# IPNS_v0_2.net
KiCad netlist of a schematic drawn in EAGLE
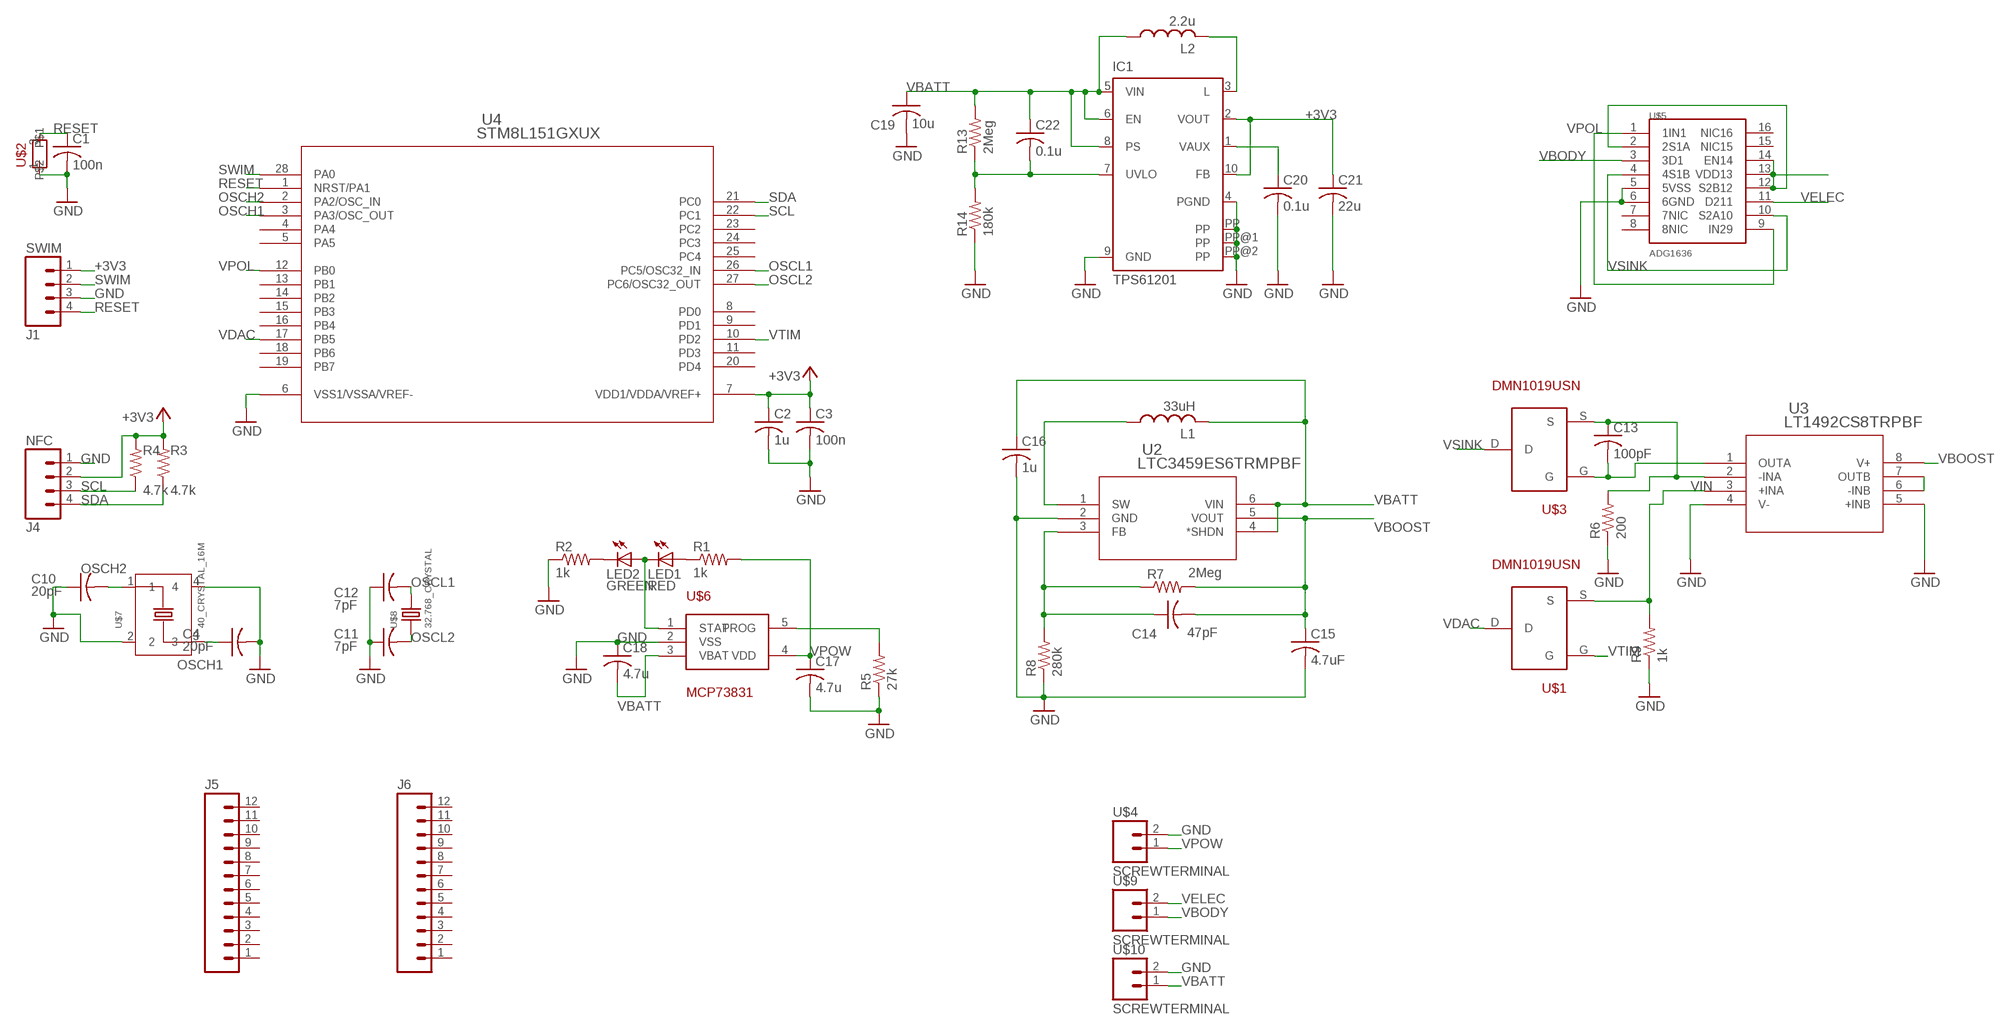
[diagram p0: schematic, sheet 1]

(export (version "E")
  (design (tool "Eeschema 10.0.6"))
  (components
    (comp (ref "C1")
      (value "100n")
      (footprint "eagle-import:C0603")
      (libsource (lib "eagle-import") (part "IPNS_Lib_v0.1_C-USC0603"))
    )
    (comp (ref "C2")
      (value "1u")
      (footprint "eagle-import:C0603")
      (libsource (lib "eagle-import") (part "IPNS_Lib_v0.1_C-USC0603"))
    )
    (comp (ref "C3")
      (value "100n")
      (footprint "eagle-import:C0603")
      (libsource (lib "eagle-import") (part "IPNS_Lib_v0.1_C-USC0603"))
    )
    (comp (ref "C4")
      (value "20pF")
      (footprint "eagle-import:C0603")
      (libsource (lib "eagle-import") (part "IPNS_Lib_v0.1_C-USC0603"))
    )
    (comp (ref "C10")
      (value "20pF")
      (footprint "eagle-import:C0603")
      (libsource (lib "eagle-import") (part "IPNS_Lib_v0.1_C-USC0603"))
    )
    (comp (ref "C11")
      (value "7pF")
      (footprint "eagle-import:C0603")
      (libsource (lib "eagle-import") (part "IPNS_Lib_v0.1_C-USC0603"))
    )
    (comp (ref "C12")
      (value "7pF")
      (footprint "eagle-import:C0603")
      (libsource (lib "eagle-import") (part "IPNS_Lib_v0.1_C-USC0603"))
    )
    (comp (ref "C13")
      (value "100pF")
      (footprint "eagle-import:C0603")
      (libsource (lib "eagle-import") (part "IPNS_Lib_v0.1_C-USC0603"))
    )
    (comp (ref "C14")
      (value "47pF")
      (footprint "eagle-import:C0603")
      (libsource (lib "eagle-import") (part "IPNS_Lib_v0.1_C-USC0603"))
    )
    (comp (ref "C15")
      (value "4.7uF")
      (footprint "eagle-import:C0603")
      (libsource (lib "eagle-import") (part "IPNS_Lib_v0.1_C-USC0603"))
    )
    (comp (ref "C16")
      (value "1u")
      (footprint "eagle-import:C0603")
      (libsource (lib "eagle-import") (part "IPNS_Lib_v0.1_C-USC0603"))
    )
    (comp (ref "C17")
      (value "4.7u")
      (footprint "eagle-import:C0603")
      (libsource (lib "eagle-import") (part "C-USC0603"))
    )
    (comp (ref "C18")
      (value "4.7u")
      (footprint "eagle-import:C0603")
      (libsource (lib "eagle-import") (part "C-USC0603"))
    )
    (comp (ref "C19")
      (value "10u")
      (footprint "eagle-import:C0603")
      (libsource (lib "eagle-import") (part "C-USC0603"))
    )
    (comp (ref "C20")
      (value "0.1u")
      (footprint "eagle-import:C0603")
      (libsource (lib "eagle-import") (part "rcl_C-USC0603"))
    )
    (comp (ref "C21")
      (value "22u")
      (footprint "eagle-import:C0603")
      (libsource (lib "eagle-import") (part "rcl_C-USC0603"))
    )
    (comp (ref "C22")
      (value "0.1u")
      (footprint "eagle-import:C0603")
      (libsource (lib "eagle-import") (part "rcl_C-USC0603"))
    )
    (comp (ref "IC1")
      (value "TPS61201")
      (footprint "eagle-import:S-PDSO-N10")
      (fields (field (name "MPN") "TPS61200DRCT"))
      (libsource (lib "eagle-import") (part "TPS61200"))
    )
    (comp (ref "J1")
      (value "SWIM")
      (footprint "eagle-import:1X04")
      (libsource (lib "eagle-import") (part "M04PTH"))
    )
    (comp (ref "J4")
      (value "NFC")
      (footprint "eagle-import:1X04")
      (libsource (lib "eagle-import") (part "M04PTH"))
    )
    (comp (ref "J5")
      (value "M12PTH")
      (footprint "eagle-import:1X12")
      (libsource (lib "eagle-import") (part "M12PTH"))
    )
    (comp (ref "J6")
      (value "M12PTH")
      (footprint "eagle-import:1X12")
      (libsource (lib "eagle-import") (part "M12PTH"))
    )
    (comp (ref "L1")
      (value "33uH")
      (footprint "eagle-import:L2012C")
      (libsource (lib "eagle-import") (part "L-USL2012C"))
    )
    (comp (ref "L2")
      (value "2.2u")
      (footprint "eagle-import:L2012C")
      (libsource (lib "eagle-import") (part "rcl_L-USL2012C"))
    )
    (comp (ref "LED1")
      (value "RED")
      (footprint "eagle-import:SML0603")
      (libsource (lib "eagle-import") (part "LEDSML0603"))
    )
    (comp (ref "LED2")
      (value "GREEN")
      (footprint "eagle-import:SML0603")
      (libsource (lib "eagle-import") (part "LEDSML0603"))
    )
    (comp (ref "R1")
      (value "1k")
      (footprint "eagle-import:R0603")
      (libsource (lib "eagle-import") (part "R-US_R0603"))
    )
    (comp (ref "R2")
      (value "1k")
      (footprint "eagle-import:R0603")
      (libsource (lib "eagle-import") (part "R-US_R0603"))
    )
    (comp (ref "R3")
      (value "4.7k")
      (footprint "eagle-import:R0603")
      (libsource (lib "eagle-import") (part "IPNS_Lib_v0.1_R-US_R0603"))
    )
    (comp (ref "R4")
      (value "4.7k")
      (footprint "eagle-import:R0603")
      (libsource (lib "eagle-import") (part "IPNS_Lib_v0.1_R-US_R0603"))
    )
    (comp (ref "R5")
      (value "27k")
      (footprint "eagle-import:R0603")
      (libsource (lib "eagle-import") (part "R-US_R0603"))
    )
    (comp (ref "R6")
      (value "200")
      (footprint "eagle-import:R0603")
      (libsource (lib "eagle-import") (part "IPNS_Lib_v0.1_R-US_R0603"))
    )
    (comp (ref "R7")
      (value "2Meg")
      (footprint "eagle-import:R0603")
      (libsource (lib "eagle-import") (part "IPNS_Lib_v0.1_R-US_R0603"))
    )
    (comp (ref "R8")
      (value "280k")
      (footprint "eagle-import:R0603")
      (libsource (lib "eagle-import") (part "IPNS_Lib_v0.1_R-US_R0603"))
    )
    (comp (ref "R9")
      (value "1k")
      (footprint "eagle-import:R0603")
      (libsource (lib "eagle-import") (part "IPNS_Lib_v0.1_R-US_R0603"))
    )
    (comp (ref "R13")
      (value "2Meg")
      (footprint "eagle-import:R0603")
      (libsource (lib "eagle-import") (part "rcl_R-US_R0603"))
    )
    (comp (ref "R14")
      (value "180k")
      (footprint "eagle-import:R0603")
      (libsource (lib "eagle-import") (part "rcl_R-US_R0603"))
    )
    (comp (ref "U$1")
      (value "DMN1019USN")
      (footprint "eagle-import:DMN1019USN")
      (libsource (lib "eagle-import") (part "DMN1019USN"))
    )
    (comp (ref "U$2")
      (value "PUSH-BUTTON")
      (footprint "eagle-import:PUSH-BUTTON")
      (libsource (lib "eagle-import") (part "PUSH-BUTTON"))
    )
    (comp (ref "U$3")
      (value "DMN1019USN")
      (footprint "eagle-import:DMN1019USN")
      (libsource (lib "eagle-import") (part "DMN1019USN"))
    )
    (comp (ref "U$4")
      (value "SCREWTERMINAL")
      (footprint "eagle-import:SCREWTERMINAL")
      (libsource (lib "eagle-import") (part "SCREWTERMINAL"))
    )
    (comp (ref "U$5")
      (value "ADG1636")
      (footprint "eagle-import:TSSOP16")
      (libsource (lib "eagle-import") (part "ADG1636"))
    )
    (comp (ref "U$6")
      (value "MCP78381")
      (footprint "eagle-import:SOT23-5L")
      (libsource (lib "eagle-import") (part "MCP78381"))
    )
    (comp (ref "U$7")
      (value "40_CRYSTAL_16M")
      (footprint "eagle-import:X4-SMD-3.2X2.5X0.7MM")
      (libsource (lib "eagle-import") (part "40_CRYSTAL_16M"))
    )
    (comp (ref "U$8")
      (value "32.768_CRYSTAL")
      (footprint "eagle-import:X2-SMD-3.2X1.5X0.55MM")
      (libsource (lib "eagle-import") (part "32.768_CRYSTAL"))
    )
    (comp (ref "U$9")
      (value "SCREWTERMINAL")
      (footprint "eagle-import:SCREWTERMINAL")
      (libsource (lib "eagle-import") (part "SCREWTERMINAL"))
    )
    (comp (ref "U$10")
      (value "SCREWTERMINAL")
      (footprint "eagle-import:SCREWTERMINAL")
      (libsource (lib "eagle-import") (part "SCREWTERMINAL"))
    )
    (comp (ref "U2")
      (value "LTC3459ES6TRMPBF")
      (footprint "eagle-import:TSOT-23_S6")
      (fields
        (field (name "MANUFACTURER_PART_NUMBER") "ltc3459es6#trmpbf")
        (field (name "COPYRIGHT") "Copyright (C) 2016 Accelerated Designs. All rights reserved")
      )
      (libsource (lib "eagle-import") (part "LTC3459ES6TRMPBF"))
    )
    (comp (ref "U3")
      (value "LT1492CS8TRPBF")
      (footprint "eagle-import:SO-8_S")
      (fields (field (name "MANUFACTURER_PART_NUMBER") "lt1492cs8#trpbf"))
      (libsource (lib "eagle-import") (part "LT1492CS8TRPBF"))
    )
    (comp (ref "U4")
      (value "STM8L151GXUX")
      (footprint "eagle-import:UFQFPN-28")
      (fields
        (field (name "MANUFACTURER_PART_NUMBER") "stm8l151gxux")
        (field (name "COPYRIGHT") "Copyright (C) 2016 Accelerated Designs. All rights reserved")
      )
      (libsource (lib "eagle-import") (part "STM8L151GXUX"))
    )
  )
  (nets
    (net (code "1") (name "+3V3") (class "Default")
      (node (ref "C2") (pin "1") (pinfunction "1_1") (pintype "passive"))
      (node (ref "C21") (pin "1") (pinfunction "1_1") (pintype "passive"))
      (node (ref "C3") (pin "1") (pinfunction "1_1") (pintype "passive"))
      (node (ref "IC1") (pin "10") (pinfunction "FB_10") (pintype "input"))
      (node (ref "IC1") (pin "2") (pinfunction "VOUT_2") (pintype "passive"))
      (node (ref "J1") (pin "1") (pinfunction "1_1") (pintype "passive"))
      (node (ref "J4") (pin "2") (pinfunction "2_2") (pintype "passive"))
      (node (ref "R3") (pin "2") (pinfunction "2_2") (pintype "passive"))
      (node (ref "R4") (pin "2") (pinfunction "2_2") (pintype "passive"))
      (node (ref "U4") (pin "7") (pinfunction "VDD1/VDDA/VREF+_7") (pintype "power_in"))
    )
    (net (code "2") (name "/OSCH1") (class "Default")
      (node (ref "C4") (pin "1") (pinfunction "1_1") (pintype "passive"))
      (node (ref "U$7") (pin "3") (pinfunction "3_3") (pintype "bidirectional"))
      (node (ref "U4") (pin "3") (pinfunction "PA3/OSC_OUT_3") (pintype "bidirectional"))
    )
    (net (code "3") (name "/OSCH2") (class "Default")
      (node (ref "C10") (pin "2") (pinfunction "2_2") (pintype "passive"))
      (node (ref "U$7") (pin "1") (pinfunction "1_1") (pintype "bidirectional"))
      (node (ref "U4") (pin "2") (pinfunction "PA2/OSC_IN_2") (pintype "bidirectional"))
    )
    (net (code "4") (name "/OSCL1") (class "Default")
      (node (ref "C12") (pin "2") (pinfunction "2_2") (pintype "passive"))
      (node (ref "U$8") (pin "2") (pinfunction "2_2") (pintype "passive"))
      (node (ref "U4") (pin "26") (pinfunction "PC5/OSC32_IN_26") (pintype "bidirectional"))
    )
    (net (code "5") (name "/OSCL2") (class "Default")
      (node (ref "C11") (pin "2") (pinfunction "2_2") (pintype "passive"))
      (node (ref "U$8") (pin "1") (pinfunction "1_1") (pintype "passive"))
      (node (ref "U4") (pin "27") (pinfunction "PC6/OSC32_OUT_27") (pintype "bidirectional"))
    )
    (net (code "6") (name "/RESET") (class "Default")
      (node (ref "C1") (pin "1") (pinfunction "1_1") (pintype "passive"))
      (node (ref "J1") (pin "4") (pinfunction "4_4") (pintype "passive"))
      (node (ref "U$2") (pin "3") (pinfunction "P$2_3") (pintype "bidirectional"))
      (node (ref "U4") (pin "1") (pinfunction "NRST/PA1_1") (pintype "bidirectional"))
    )
    (net (code "7") (name "/SCL") (class "Default")
      (node (ref "J4") (pin "3") (pinfunction "3_3") (pintype "passive"))
      (node (ref "R4") (pin "1") (pinfunction "1_1") (pintype "passive"))
      (node (ref "U4") (pin "22") (pinfunction "PC1_22") (pintype "bidirectional"))
    )
    (net (code "8") (name "/SDA") (class "Default")
      (node (ref "J4") (pin "4") (pinfunction "4_4") (pintype "passive"))
      (node (ref "R3") (pin "1") (pinfunction "1_1") (pintype "passive"))
      (node (ref "U4") (pin "21") (pinfunction "PC0_21") (pintype "bidirectional"))
    )
    (net (code "9") (name "/SWIM") (class "Default")
      (node (ref "J1") (pin "2") (pinfunction "2_2") (pintype "passive"))
      (node (ref "U4") (pin "28") (pinfunction "PA0_28") (pintype "bidirectional"))
    )
    (net (code "10") (name "/VBATT") (class "Default")
      (node (ref "C16") (pin "1") (pinfunction "1_1") (pintype "passive"))
      (node (ref "C18") (pin "2") (pinfunction "2_2") (pintype "passive"))
      (node (ref "C19") (pin "1") (pinfunction "1_1") (pintype "passive"))
      (node (ref "C22") (pin "1") (pinfunction "1_1") (pintype "passive"))
      (node (ref "IC1") (pin "5") (pinfunction "VIN_5") (pintype "input"))
      (node (ref "IC1") (pin "6") (pinfunction "EN_6") (pintype "input"))
      (node (ref "IC1") (pin "8") (pinfunction "PS_8") (pintype "input"))
      (node (ref "L1") (pin "2") (pinfunction "2_2") (pintype "passive"))
      (node (ref "L2") (pin "1") (pinfunction "1_1") (pintype "passive"))
      (node (ref "R13") (pin "2") (pinfunction "2_2") (pintype "passive"))
      (node (ref "U$10") (pin "1") (pinfunction "1_1") (pintype "passive"))
      (node (ref "U$6") (pin "3") (pinfunction "VBAT_3") (pintype "bidirectional"))
      (node (ref "U2") (pin "4") (pinfunction "*SHDN_4") (pintype "input"))
      (node (ref "U2") (pin "6") (pinfunction "VIN_6") (pintype "input"))
    )
    (net (code "11") (name "/VBODY") (class "Default")
      (node (ref "U$5") (pin "3") (pinfunction "3D1_3") (pintype "bidirectional"))
      (node (ref "U$9") (pin "1") (pinfunction "1_1") (pintype "passive"))
    )
    (net (code "12") (name "/VBOOST") (class "Default")
      (node (ref "C14") (pin "2") (pinfunction "2_2") (pintype "passive"))
      (node (ref "C15") (pin "1") (pinfunction "1_1") (pintype "passive"))
      (node (ref "R7") (pin "2") (pinfunction "2_2") (pintype "passive"))
      (node (ref "U2") (pin "5") (pinfunction "VOUT_5") (pintype "output"))
      (node (ref "U3") (pin "8") (pinfunction "V+_8") (pintype "power_in"))
    )
    (net (code "13") (name "/VDAC") (class "Default")
      (node (ref "U$1") (pin "D") (pinfunction "D_D") (pintype "bidirectional"))
      (node (ref "U4") (pin "17") (pinfunction "PB5_17") (pintype "bidirectional"))
    )
    (net (code "14") (name "/VELEC") (class "Default")
      (node (ref "U$5") (pin "11") (pinfunction "D211_11") (pintype "bidirectional"))
      (node (ref "U$9") (pin "2") (pinfunction "2_2") (pintype "passive"))
    )
    (net (code "15") (name "/VIN") (class "Default")
      (node (ref "R9") (pin "2") (pinfunction "2_2") (pintype "passive"))
      (node (ref "U$1") (pin "S") (pinfunction "S_S") (pintype "bidirectional"))
      (node (ref "U3") (pin "3") (pinfunction "+INA_3") (pintype "input"))
    )
    (net (code "16") (name "/VPOL") (class "Default")
      (node (ref "U$5") (pin "1") (pinfunction "1IN1_1") (pintype "bidirectional"))
      (node (ref "U$5") (pin "9") (pinfunction "IN29_9") (pintype "bidirectional"))
      (node (ref "U4") (pin "12") (pinfunction "PB0_12") (pintype "bidirectional"))
    )
    (net (code "17") (name "/VPOW") (class "Default")
      (node (ref "C17") (pin "1") (pinfunction "1_1") (pintype "passive"))
      (node (ref "R1") (pin "2") (pinfunction "2_2") (pintype "passive"))
      (node (ref "U$4") (pin "1") (pinfunction "1_1") (pintype "passive"))
      (node (ref "U$6") (pin "4") (pinfunction "VDD_4") (pintype "bidirectional"))
    )
    (net (code "18") (name "/VSINK") (class "Default")
      (node (ref "U$3") (pin "D") (pinfunction "D_D") (pintype "bidirectional"))
      (node (ref "U$5") (pin "10") (pinfunction "S2A10_10") (pintype "bidirectional"))
      (node (ref "U$5") (pin "4") (pinfunction "4S1B_4") (pintype "bidirectional"))
    )
    (net (code "19") (name "/VTIM") (class "Default")
      (node (ref "U$1") (pin "G") (pinfunction "G_G") (pintype "bidirectional"))
      (node (ref "U4") (pin "10") (pinfunction "PD2_10") (pintype "bidirectional"))
    )
    (net (code "20") (name "GND") (class "Default")
      (node (ref "C1") (pin "2") (pinfunction "2_2") (pintype "passive"))
      (node (ref "C10") (pin "1") (pinfunction "1_1") (pintype "passive"))
      (node (ref "C11") (pin "1") (pinfunction "1_1") (pintype "passive"))
      (node (ref "C12") (pin "1") (pinfunction "1_1") (pintype "passive"))
      (node (ref "C15") (pin "2") (pinfunction "2_2") (pintype "passive"))
      (node (ref "C16") (pin "2") (pinfunction "2_2") (pintype "passive"))
      (node (ref "C17") (pin "2") (pinfunction "2_2") (pintype "passive"))
      (node (ref "C18") (pin "1") (pinfunction "1_1") (pintype "passive"))
      (node (ref "C19") (pin "2") (pinfunction "2_2") (pintype "passive"))
      (node (ref "C2") (pin "2") (pinfunction "2_2") (pintype "passive"))
      (node (ref "C20") (pin "2") (pinfunction "2_2") (pintype "passive"))
      (node (ref "C21") (pin "2") (pinfunction "2_2") (pintype "passive"))
      (node (ref "C3") (pin "2") (pinfunction "2_2") (pintype "passive"))
      (node (ref "C4") (pin "2") (pinfunction "2_2") (pintype "passive"))
      (node (ref "IC1") (pin "4") (pinfunction "PGND_4") (pintype "power_in"))
      (node (ref "IC1") (pin "9") (pinfunction "GND_9") (pintype "power_in"))
      (node (ref "IC1") (pin "PP") (pinfunction "PP_PP") (pintype "power_in"))
      (node (ref "IC1") (pin "PP@1") (pinfunction "PP_PP@1") (pintype "power_in"))
      (node (ref "IC1") (pin "PP@2") (pinfunction "PP_PP@2") (pintype "power_in"))
      (node (ref "J1") (pin "3") (pinfunction "3_3") (pintype "passive"))
      (node (ref "J4") (pin "1") (pinfunction "1_1") (pintype "passive"))
      (node (ref "R14") (pin "1") (pinfunction "1_1") (pintype "passive"))
      (node (ref "R2") (pin "1") (pinfunction "1_1") (pintype "passive"))
      (node (ref "R5") (pin "1") (pinfunction "1_1") (pintype "passive"))
      (node (ref "R6") (pin "1") (pinfunction "1_1") (pintype "passive"))
      (node (ref "R8") (pin "1") (pinfunction "1_1") (pintype "passive"))
      (node (ref "R9") (pin "1") (pinfunction "1_1") (pintype "passive"))
      (node (ref "U$10") (pin "2") (pinfunction "2_2") (pintype "passive"))
      (node (ref "U$2") (pin "1") (pinfunction "P$1_1") (pintype "bidirectional"))
      (node (ref "U$4") (pin "2") (pinfunction "2_2") (pintype "passive"))
      (node (ref "U$5") (pin "5") (pinfunction "5VSS_5") (pintype "bidirectional"))
      (node (ref "U$5") (pin "6") (pinfunction "6GND_6") (pintype "bidirectional"))
      (node (ref "U$6") (pin "2") (pinfunction "VSS_2") (pintype "bidirectional"))
      (node (ref "U$7") (pin "2") (pinfunction "2_2") (pintype "bidirectional"))
      (node (ref "U$7") (pin "4") (pinfunction "4_4") (pintype "bidirectional"))
      (node (ref "U2") (pin "2") (pinfunction "GND_2") (pintype "power_in"))
      (node (ref "U3") (pin "4") (pinfunction "V-_4") (pintype "power_in"))
      (node (ref "U3") (pin "5") (pinfunction "+INB_5") (pintype "input"))
      (node (ref "U4") (pin "6") (pinfunction "VSS1/VSSA/VREF-_6") (pintype "power_in"))
    )
    (net (code "21") (name "Net-(IC1-L)") (class "Default")
      (node (ref "IC1") (pin "3") (pinfunction "L_3") (pintype "input"))
      (node (ref "L2") (pin "2") (pinfunction "2_2") (pintype "passive"))
    )
    (net (code "22") (name "Net-(IC1-UVLO)") (class "Default")
      (node (ref "C22") (pin "2") (pinfunction "2_2") (pintype "passive"))
      (node (ref "IC1") (pin "7") (pinfunction "UVLO_7") (pintype "input"))
      (node (ref "R13") (pin "1") (pinfunction "1_1") (pintype "passive"))
      (node (ref "R14") (pin "2") (pinfunction "2_2") (pintype "passive"))
    )
    (net (code "23") (name "Net-(IC1-VAUX)") (class "Default")
      (node (ref "C20") (pin "1") (pinfunction "1_1") (pintype "passive"))
      (node (ref "IC1") (pin "1") (pinfunction "VAUX_1") (pintype "bidirectional"))
    )
    (net (code "24") (name "Net-(LED1-PadA)") (class "Default")
      (node (ref "LED1") (pin "A") (pinfunction "A_A") (pintype "passive"))
      (node (ref "R1") (pin "1") (pinfunction "1_1") (pintype "passive"))
    )
    (net (code "25") (name "Net-(LED2-PadC)") (class "Default")
      (node (ref "LED2") (pin "C") (pinfunction "C_C") (pintype "passive"))
      (node (ref "R2") (pin "2") (pinfunction "2_2") (pintype "passive"))
    )
    (net (code "26") (name "Net-(U$5-2S1A)") (class "Default")
      (node (ref "U$5") (pin "12") (pinfunction "S2B12_12") (pintype "bidirectional"))
      (node (ref "U$5") (pin "13") (pinfunction "VDD13_13") (pintype "bidirectional"))
      (node (ref "U$5") (pin "14") (pinfunction "EN14_14") (pintype "bidirectional"))
      (node (ref "U$5") (pin "2") (pinfunction "2S1A_2") (pintype "bidirectional"))
    )
    (net (code "27") (name "Net-(U$6-PROG)") (class "Default")
      (node (ref "R5") (pin "2") (pinfunction "2_2") (pintype "passive"))
      (node (ref "U$6") (pin "5") (pinfunction "PROG_5") (pintype "bidirectional"))
    )
    (net (code "28") (name "Net-(U$6-STAT)") (class "Default")
      (node (ref "LED1") (pin "C") (pinfunction "C_C") (pintype "passive"))
      (node (ref "LED2") (pin "A") (pinfunction "A_A") (pintype "passive"))
      (node (ref "U$6") (pin "1") (pinfunction "STAT_1") (pintype "bidirectional"))
    )
    (net (code "29") (name "Net-(U2-FB)") (class "Default")
      (node (ref "C14") (pin "1") (pinfunction "1_1") (pintype "passive"))
      (node (ref "R7") (pin "1") (pinfunction "1_1") (pintype "passive"))
      (node (ref "R8") (pin "2") (pinfunction "2_2") (pintype "passive"))
      (node (ref "U2") (pin "3") (pinfunction "FB_3") (pintype "input"))
    )
    (net (code "30") (name "Net-(U2-SW)") (class "Default")
      (node (ref "L1") (pin "1") (pinfunction "1_1") (pintype "passive"))
      (node (ref "U2") (pin "1") (pinfunction "SW_1") (pintype "passive"))
    )
    (net (code "31") (name "Net-(U3--INA)") (class "Default")
      (node (ref "C13") (pin "1") (pinfunction "1_1") (pintype "passive"))
      (node (ref "R6") (pin "2") (pinfunction "2_2") (pintype "passive"))
      (node (ref "U$3") (pin "S") (pinfunction "S_S") (pintype "bidirectional"))
      (node (ref "U3") (pin "2") (pinfunction "-INA_2") (pintype "input"))
    )
    (net (code "32") (name "Net-(U3--INB)") (class "Default")
      (node (ref "U3") (pin "6") (pinfunction "-INB_6") (pintype "input"))
      (node (ref "U3") (pin "7") (pinfunction "OUTB_7") (pintype "output"))
    )
    (net (code "33") (name "Net-(U3-OUTA)") (class "Default")
      (node (ref "C13") (pin "2") (pinfunction "2_2") (pintype "passive"))
      (node (ref "U$3") (pin "G") (pinfunction "G_G") (pintype "bidirectional"))
      (node (ref "U3") (pin "1") (pinfunction "OUTA_1") (pintype "output"))
    )
    (net (code "34") (name "unconnected-(J5-Pad1)") (class "Default")
      (node (ref "J5") (pin "1") (pinfunction "1_1") (pintype "passive"))
    )
    (net (code "35") (name "unconnected-(J5-Pad2)") (class "Default")
      (node (ref "J5") (pin "2") (pinfunction "2_2") (pintype "passive"))
    )
    (net (code "36") (name "unconnected-(J5-Pad3)") (class "Default")
      (node (ref "J5") (pin "3") (pinfunction "3_3") (pintype "passive"))
    )
    (net (code "37") (name "unconnected-(J5-Pad4)") (class "Default")
      (node (ref "J5") (pin "4") (pinfunction "4_4") (pintype "passive"))
    )
    (net (code "38") (name "unconnected-(J5-Pad5)") (class "Default")
      (node (ref "J5") (pin "5") (pinfunction "5_5") (pintype "passive"))
    )
    (net (code "39") (name "unconnected-(J5-Pad6)") (class "Default")
      (node (ref "J5") (pin "6") (pinfunction "6_6") (pintype "passive"))
    )
    (net (code "40") (name "unconnected-(J5-Pad7)") (class "Default")
      (node (ref "J5") (pin "7") (pinfunction "7_7") (pintype "passive"))
    )
    (net (code "41") (name "unconnected-(J5-Pad8)") (class "Default")
      (node (ref "J5") (pin "8") (pinfunction "8_8") (pintype "passive"))
    )
    (net (code "42") (name "unconnected-(J5-Pad9)") (class "Default")
      (node (ref "J5") (pin "9") (pinfunction "9_9") (pintype "passive"))
    )
    (net (code "43") (name "unconnected-(J5-Pad10)") (class "Default")
      (node (ref "J5") (pin "10") (pinfunction "10_10") (pintype "passive"))
    )
    (net (code "44") (name "unconnected-(J5-Pad11)") (class "Default")
      (node (ref "J5") (pin "11") (pinfunction "11_11") (pintype "passive"))
    )
    (net (code "45") (name "unconnected-(J5-Pad12)") (class "Default")
      (node (ref "J5") (pin "12") (pinfunction "12_12") (pintype "passive"))
    )
    (net (code "46") (name "unconnected-(J6-Pad1)") (class "Default")
      (node (ref "J6") (pin "1") (pinfunction "1_1") (pintype "passive"))
    )
    (net (code "47") (name "unconnected-(J6-Pad2)") (class "Default")
      (node (ref "J6") (pin "2") (pinfunction "2_2") (pintype "passive"))
    )
    (net (code "48") (name "unconnected-(J6-Pad3)") (class "Default")
      (node (ref "J6") (pin "3") (pinfunction "3_3") (pintype "passive"))
    )
    (net (code "49") (name "unconnected-(J6-Pad4)") (class "Default")
      (node (ref "J6") (pin "4") (pinfunction "4_4") (pintype "passive"))
    )
    (net (code "50") (name "unconnected-(J6-Pad5)") (class "Default")
      (node (ref "J6") (pin "5") (pinfunction "5_5") (pintype "passive"))
    )
    (net (code "51") (name "unconnected-(J6-Pad6)") (class "Default")
      (node (ref "J6") (pin "6") (pinfunction "6_6") (pintype "passive"))
    )
    (net (code "52") (name "unconnected-(J6-Pad7)") (class "Default")
      (node (ref "J6") (pin "7") (pinfunction "7_7") (pintype "passive"))
    )
    (net (code "53") (name "unconnected-(J6-Pad8)") (class "Default")
      (node (ref "J6") (pin "8") (pinfunction "8_8") (pintype "passive"))
    )
    (net (code "54") (name "unconnected-(J6-Pad9)") (class "Default")
      (node (ref "J6") (pin "9") (pinfunction "9_9") (pintype "passive"))
    )
    (net (code "55") (name "unconnected-(J6-Pad10)") (class "Default")
      (node (ref "J6") (pin "10") (pinfunction "10_10") (pintype "passive"))
    )
    (net (code "56") (name "unconnected-(J6-Pad11)") (class "Default")
      (node (ref "J6") (pin "11") (pinfunction "11_11") (pintype "passive"))
    )
    (net (code "57") (name "unconnected-(J6-Pad12)") (class "Default")
      (node (ref "J6") (pin "12") (pinfunction "12_12") (pintype "passive"))
    )
    (net (code "58") (name "unconnected-(U$5-7NIC-Pad7)") (class "Default")
      (node (ref "U$5") (pin "7") (pinfunction "7NIC_7") (pintype "bidirectional"))
    )
    (net (code "59") (name "unconnected-(U$5-8NIC-Pad8)") (class "Default")
      (node (ref "U$5") (pin "8") (pinfunction "8NIC_8") (pintype "bidirectional"))
    )
    (net (code "60") (name "unconnected-(U$5-NIC15-Pad15)") (class "Default")
      (node (ref "U$5") (pin "15") (pinfunction "NIC15_15") (pintype "bidirectional"))
    )
    (net (code "61") (name "unconnected-(U$5-NIC16-Pad16)") (class "Default")
      (node (ref "U$5") (pin "16") (pinfunction "NIC16_16") (pintype "bidirectional"))
    )
    (net (code "62") (name "unconnected-(U4-PA4-Pad4)") (class "Default")
      (node (ref "U4") (pin "4") (pinfunction "PA4_4") (pintype "bidirectional"))
    )
    (net (code "63") (name "unconnected-(U4-PA5-Pad5)") (class "Default")
      (node (ref "U4") (pin "5") (pinfunction "PA5_5") (pintype "bidirectional"))
    )
    (net (code "64") (name "unconnected-(U4-PB1-Pad13)") (class "Default")
      (node (ref "U4") (pin "13") (pinfunction "PB1_13") (pintype "bidirectional"))
    )
    (net (code "65") (name "unconnected-(U4-PB2-Pad14)") (class "Default")
      (node (ref "U4") (pin "14") (pinfunction "PB2_14") (pintype "bidirectional"))
    )
    (net (code "66") (name "unconnected-(U4-PB3-Pad15)") (class "Default")
      (node (ref "U4") (pin "15") (pinfunction "PB3_15") (pintype "bidirectional"))
    )
    (net (code "67") (name "unconnected-(U4-PB4-Pad16)") (class "Default")
      (node (ref "U4") (pin "16") (pinfunction "PB4_16") (pintype "bidirectional"))
    )
    (net (code "68") (name "unconnected-(U4-PB6-Pad18)") (class "Default")
      (node (ref "U4") (pin "18") (pinfunction "PB6_18") (pintype "bidirectional"))
    )
    (net (code "69") (name "unconnected-(U4-PB7-Pad19)") (class "Default")
      (node (ref "U4") (pin "19") (pinfunction "PB7_19") (pintype "bidirectional"))
    )
    (net (code "70") (name "unconnected-(U4-PC2-Pad23)") (class "Default")
      (node (ref "U4") (pin "23") (pinfunction "PC2_23") (pintype "bidirectional"))
    )
    (net (code "71") (name "unconnected-(U4-PC3-Pad24)") (class "Default")
      (node (ref "U4") (pin "24") (pinfunction "PC3_24") (pintype "bidirectional"))
    )
    (net (code "72") (name "unconnected-(U4-PC4-Pad25)") (class "Default")
      (node (ref "U4") (pin "25") (pinfunction "PC4_25") (pintype "bidirectional"))
    )
    (net (code "73") (name "unconnected-(U4-PD0-Pad8)") (class "Default")
      (node (ref "U4") (pin "8") (pinfunction "PD0_8") (pintype "bidirectional"))
    )
    (net (code "74") (name "unconnected-(U4-PD1-Pad9)") (class "Default")
      (node (ref "U4") (pin "9") (pinfunction "PD1_9") (pintype "bidirectional"))
    )
    (net (code "75") (name "unconnected-(U4-PD3-Pad11)") (class "Default")
      (node (ref "U4") (pin "11") (pinfunction "PD3_11") (pintype "bidirectional"))
    )
    (net (code "76") (name "unconnected-(U4-PD4-Pad20)") (class "Default")
      (node (ref "U4") (pin "20") (pinfunction "PD4_20") (pintype "bidirectional"))
    )
  )
)
